# LED-PCB_DIG0.net
KiCad netlist of a schematic drawn in Altium Designer
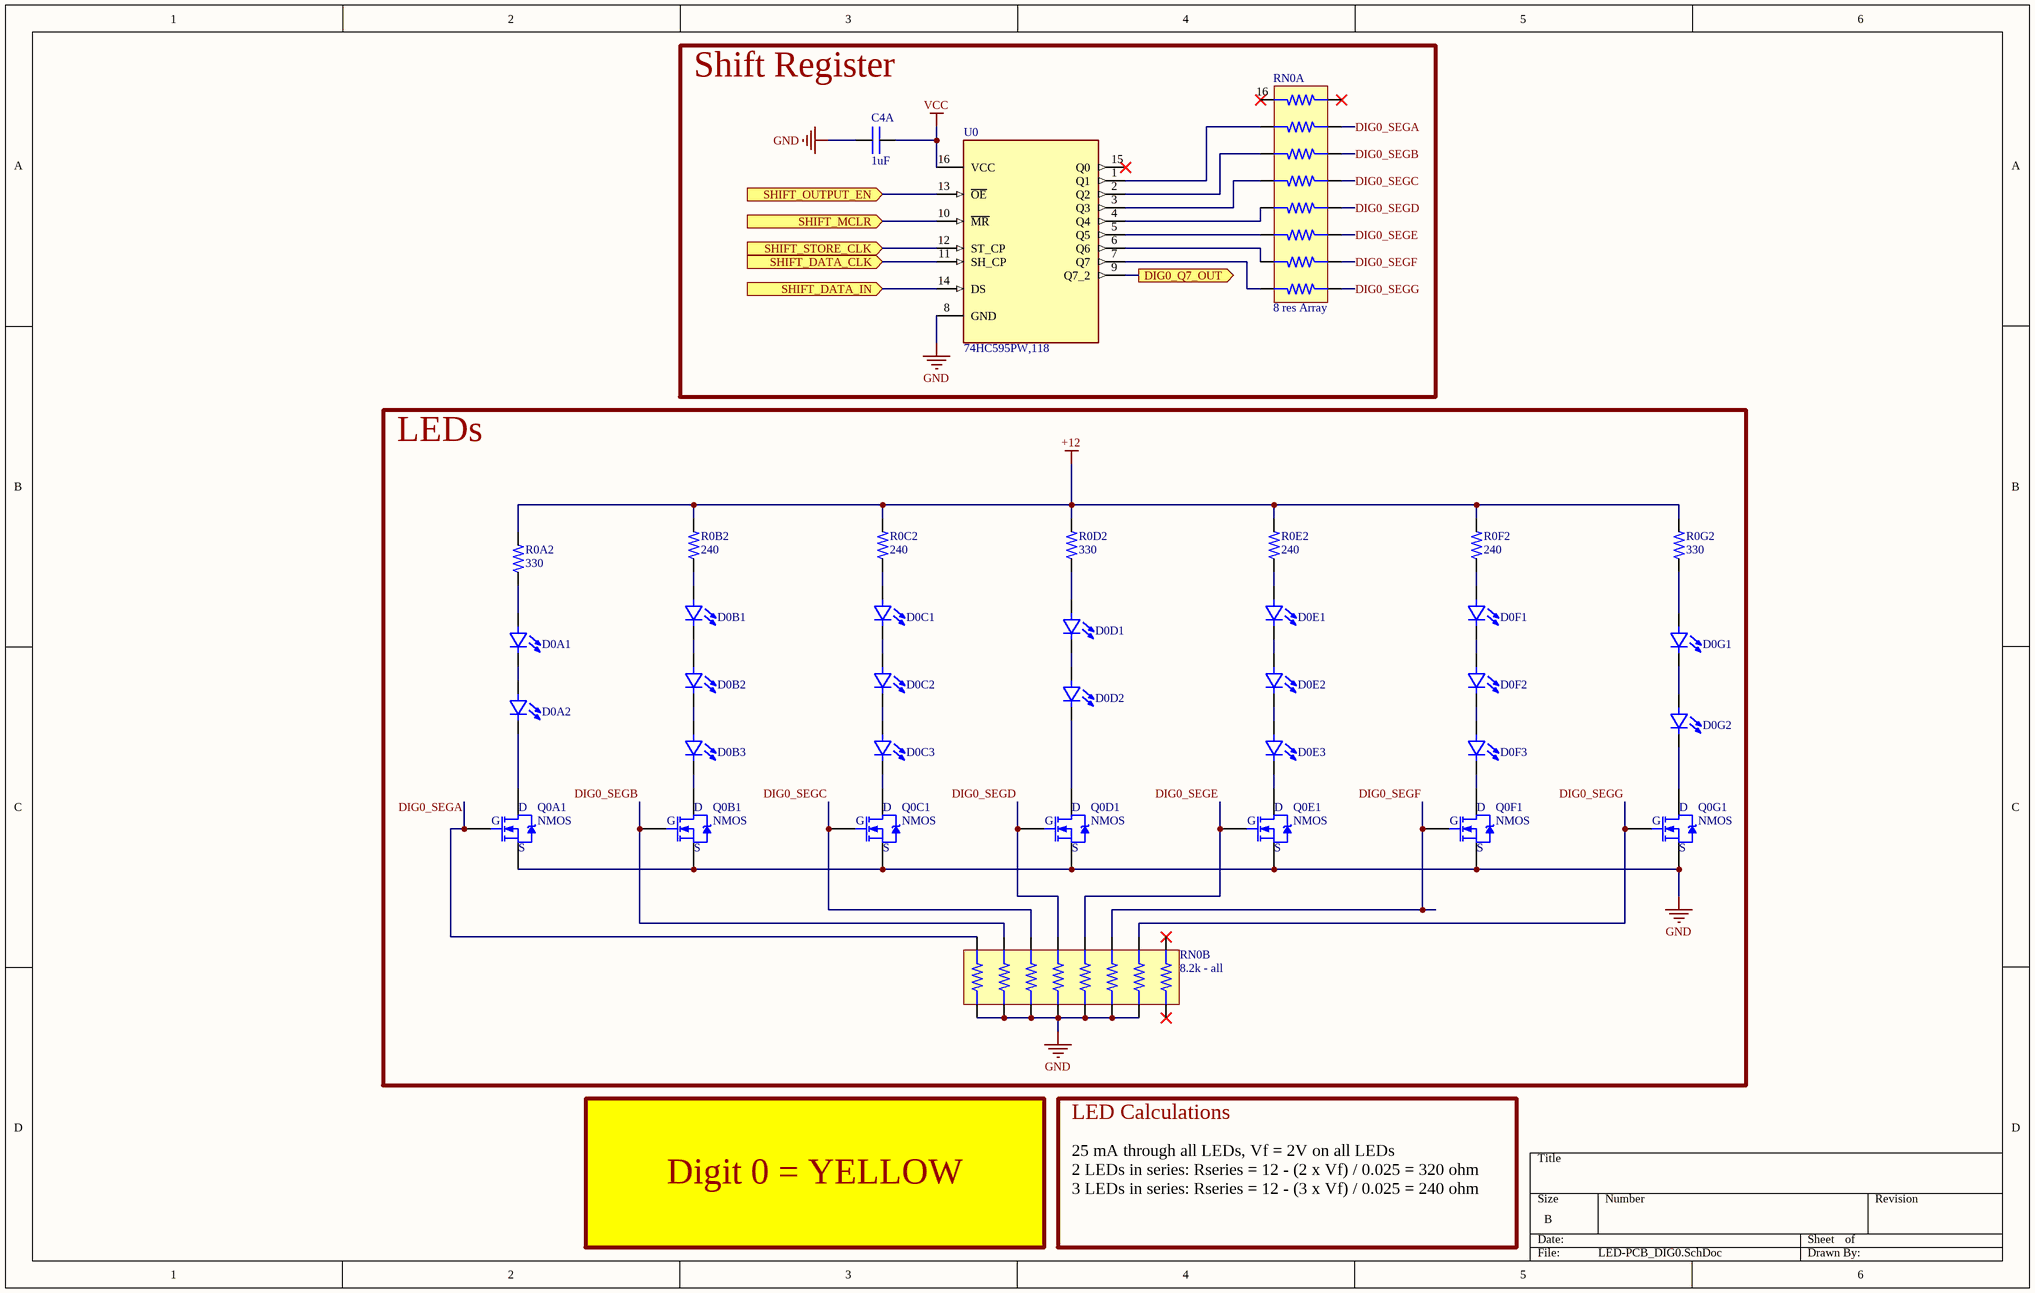
[diagram p0: LED-PCB_DIG0.SchDoc]

(export (version "E")
  (design (tool "Eeschema 10.0.6"))
  (components
    (comp (ref "C4A")
      (value "1uF")
      (footprint "sinking-clock:0402 CAP")
      (description "Capaicitor")
      (fields (field (name "PART NUMBER") "CL05A105KP5NNNC") (field (name "Comment") "CAP"))
      (libsource (lib "sinking-clock") (part "CAP"))
    )
    (comp (ref "D0A1")
      (value "LED - single")
      (footprint "sinking-clock:LED - 0603")
      (fields (field (name "PART NUMBER") "150060RS75000"))
      (libsource (lib "sinking-clock") (part "LED - single"))
    )
    (comp (ref "D0A2")
      (value "LED - single")
      (footprint "sinking-clock:LED - 0603")
      (fields (field (name "PART NUMBER") "150060RS75000"))
      (libsource (lib "sinking-clock") (part "LED - single"))
    )
    (comp (ref "D0B1")
      (value "LED - single")
      (footprint "sinking-clock:LED - 0603")
      (fields (field (name "PART NUMBER") "150060RS75000"))
      (libsource (lib "sinking-clock") (part "LED - single"))
    )
    (comp (ref "D0B2")
      (value "LED - single")
      (footprint "sinking-clock:LED - 0603")
      (fields (field (name "PART NUMBER") "150060RS75000"))
      (libsource (lib "sinking-clock") (part "LED - single"))
    )
    (comp (ref "D0B3")
      (value "LED - single")
      (footprint "sinking-clock:LED - 0603")
      (fields (field (name "PART NUMBER") "150060RS75000"))
      (libsource (lib "sinking-clock") (part "LED - single"))
    )
    (comp (ref "D0C1")
      (value "LED - single")
      (footprint "sinking-clock:LED - 0603")
      (fields (field (name "PART NUMBER") "150060RS75000"))
      (libsource (lib "sinking-clock") (part "LED - single"))
    )
    (comp (ref "D0C2")
      (value "LED - single")
      (footprint "sinking-clock:LED - 0603")
      (fields (field (name "PART NUMBER") "150060RS75000"))
      (libsource (lib "sinking-clock") (part "LED - single"))
    )
    (comp (ref "D0C3")
      (value "LED - single")
      (footprint "sinking-clock:LED - 0603")
      (fields (field (name "PART NUMBER") "150060RS75000"))
      (libsource (lib "sinking-clock") (part "LED - single"))
    )
    (comp (ref "D0D1")
      (value "LED - single")
      (footprint "sinking-clock:LED - 0603")
      (fields (field (name "PART NUMBER") "150060RS75000"))
      (libsource (lib "sinking-clock") (part "LED - single"))
    )
    (comp (ref "D0D2")
      (value "LED - single")
      (footprint "sinking-clock:LED - 0603")
      (fields (field (name "PART NUMBER") "150060RS75000"))
      (libsource (lib "sinking-clock") (part "LED - single"))
    )
    (comp (ref "D0E1")
      (value "LED - single")
      (footprint "sinking-clock:LED - 0603")
      (fields (field (name "PART NUMBER") "150060RS75000"))
      (libsource (lib "sinking-clock") (part "LED - single"))
    )
    (comp (ref "D0E2")
      (value "LED - single")
      (footprint "sinking-clock:LED - 0603")
      (fields (field (name "PART NUMBER") "150060RS75000"))
      (libsource (lib "sinking-clock") (part "LED - single"))
    )
    (comp (ref "D0E3")
      (value "LED - single")
      (footprint "sinking-clock:LED - 0603")
      (fields (field (name "PART NUMBER") "150060RS75000"))
      (libsource (lib "sinking-clock") (part "LED - single"))
    )
    (comp (ref "D0F1")
      (value "LED - single")
      (footprint "sinking-clock:LED - 0603")
      (fields (field (name "PART NUMBER") "150060RS75000"))
      (libsource (lib "sinking-clock") (part "LED - single"))
    )
    (comp (ref "D0F2")
      (value "LED - single")
      (footprint "sinking-clock:LED - 0603")
      (fields (field (name "PART NUMBER") "150060RS75000"))
      (libsource (lib "sinking-clock") (part "LED - single"))
    )
    (comp (ref "D0F3")
      (value "LED - single")
      (footprint "sinking-clock:LED - 0603")
      (fields (field (name "PART NUMBER") "150060RS75000"))
      (libsource (lib "sinking-clock") (part "LED - single"))
    )
    (comp (ref "D0G1")
      (value "LED - single")
      (footprint "sinking-clock:LED - 0603")
      (fields (field (name "PART NUMBER") "150060RS75000"))
      (libsource (lib "sinking-clock") (part "LED - single"))
    )
    (comp (ref "D0G2")
      (value "LED - single")
      (footprint "sinking-clock:LED - 0603")
      (fields (field (name "PART NUMBER") "150060RS75000"))
      (libsource (lib "sinking-clock") (part "LED - single"))
    )
    (comp (ref "Q0A1")
      (value "NMOS")
      (footprint "sinking-clock:SOT-23")
      (description "N-Channel MOSFET")
      (fields (field (name "PART NUMBER") "DMN63D8L"))
      (libsource (lib "sinking-clock") (part "NMOS"))
    )
    (comp (ref "Q0B1")
      (value "NMOS")
      (footprint "sinking-clock:SOT-23")
      (description "N-Channel MOSFET")
      (fields (field (name "PART NUMBER") "DMN63D8L"))
      (libsource (lib "sinking-clock") (part "NMOS"))
    )
    (comp (ref "Q0C1")
      (value "NMOS")
      (footprint "sinking-clock:SOT-23")
      (description "N-Channel MOSFET")
      (fields (field (name "PART NUMBER") "DMN63D8L"))
      (libsource (lib "sinking-clock") (part "NMOS"))
    )
    (comp (ref "Q0D1")
      (value "NMOS")
      (footprint "sinking-clock:SOT-23")
      (description "N-Channel MOSFET")
      (fields (field (name "PART NUMBER") "DMN63D8L"))
      (libsource (lib "sinking-clock") (part "NMOS"))
    )
    (comp (ref "Q0E1")
      (value "NMOS")
      (footprint "sinking-clock:SOT-23")
      (description "N-Channel MOSFET")
      (fields (field (name "PART NUMBER") "DMN63D8L"))
      (libsource (lib "sinking-clock") (part "NMOS"))
    )
    (comp (ref "Q0F1")
      (value "NMOS")
      (footprint "sinking-clock:SOT-23")
      (description "N-Channel MOSFET")
      (fields (field (name "PART NUMBER") "DMN63D8L"))
      (libsource (lib "sinking-clock") (part "NMOS"))
    )
    (comp (ref "Q0G1")
      (value "NMOS")
      (footprint "sinking-clock:SOT-23")
      (description "N-Channel MOSFET")
      (fields (field (name "PART NUMBER") "DMN63D8L"))
      (libsource (lib "sinking-clock") (part "NMOS"))
    )
    (comp (ref "R0A2")
      (value "330")
      (footprint "sinking-clock:0402 RES")
      (description "Resistor")
      (fields (field (name "PART NUMBER") "RC0402JR-13330RL") (field (name "Comment") "RES"))
      (libsource (lib "sinking-clock") (part "RES"))
    )
    (comp (ref "R0B2")
      (value "240")
      (footprint "sinking-clock:0402 RES")
      (description "Resistor")
      (fields (field (name "PART NUMBER") "RC0402FR-07240RL") (field (name "Comment") "RES"))
      (libsource (lib "sinking-clock") (part "RES"))
    )
    (comp (ref "R0C2")
      (value "240")
      (footprint "sinking-clock:0402 RES")
      (description "Resistor")
      (fields (field (name "PART NUMBER") "RC0402FR-07240RL") (field (name "Comment") "RES"))
      (libsource (lib "sinking-clock") (part "RES"))
    )
    (comp (ref "R0D2")
      (value "330")
      (footprint "sinking-clock:0402 RES")
      (description "Resistor")
      (fields (field (name "PART NUMBER") "RC0402JR-13330RL") (field (name "Comment") "RES"))
      (libsource (lib "sinking-clock") (part "RES"))
    )
    (comp (ref "R0E2")
      (value "240")
      (footprint "sinking-clock:0402 RES")
      (description "Resistor")
      (fields (field (name "PART NUMBER") "RC0402FR-07240RL") (field (name "Comment") "RES"))
      (libsource (lib "sinking-clock") (part "RES"))
    )
    (comp (ref "R0F2")
      (value "240")
      (footprint "sinking-clock:0402 RES")
      (description "Resistor")
      (fields (field (name "PART NUMBER") "RC0402FR-07240RL") (field (name "Comment") "RES"))
      (libsource (lib "sinking-clock") (part "RES"))
    )
    (comp (ref "R0G2")
      (value "330")
      (footprint "sinking-clock:0402 RES")
      (description "Resistor")
      (fields (field (name "PART NUMBER") "RC0402JR-13330RL") (field (name "Comment") "RES"))
      (libsource (lib "sinking-clock") (part "RES"))
    )
    (comp (ref "RN0A")
      (value "8 res Array")
      (footprint "sinking-clock:EXB2HV331JV")
      (libsource (lib "sinking-clock") (part "8 res Array"))
    )
    (comp (ref "RN0B")
      (value "8.2k - all")
      (footprint "sinking-clock:MNR18ERAPJ822")
      (fields (field (name "PART NUMBER") "MNR18ERAPJ822"))
      (libsource (lib "sinking-clock") (part "MNR18ERAPJ822"))
    )
    (comp (ref "U0")
      (value "74HC595PW,118")
      (footprint "sinking-clock:16-TSSOP")
      (description "Shift Shift Register 1 Element 8 Bit 16-TSSOP")
      (libsource (lib "sinking-clock") (part "74HC595PW,118"))
    )
  )
  (nets
    (net (code "1") (name "+12") (class "Default")
      (node (ref "R0A2") (pin "2") (pinfunction "2_2") (pintype "passive"))
      (node (ref "R0B2") (pin "2") (pinfunction "2_2") (pintype "passive"))
      (node (ref "R0C2") (pin "2") (pinfunction "2_2") (pintype "passive"))
      (node (ref "R0D2") (pin "2") (pinfunction "2_2") (pintype "passive"))
      (node (ref "R0E2") (pin "2") (pinfunction "2_2") (pintype "passive"))
      (node (ref "R0F2") (pin "2") (pinfunction "2_2") (pintype "passive"))
      (node (ref "R0G2") (pin "2") (pinfunction "2_2") (pintype "passive"))
    )
    (net (code "2") (name "/DIG0_Q7_OUT") (class "Default")
      (node (ref "U0") (pin "9") (pinfunction "Q7_2_9") (pintype "output"))
    )
    (net (code "3") (name "/DIG0_SEGA") (class "Default")
      (node (ref "Q0A1") (pin "1") (pinfunction "G_1") (pintype "passive"))
      (node (ref "RN0A") (pin "2") (pinfunction "2_2") (pintype "passive"))
      (node (ref "RN0B") (pin "16") (pinfunction "16_16") (pintype "passive"))
    )
    (net (code "4") (name "/DIG0_SEGB") (class "Default")
      (node (ref "Q0B1") (pin "1") (pinfunction "G_1") (pintype "passive"))
      (node (ref "RN0A") (pin "3") (pinfunction "3_3") (pintype "passive"))
      (node (ref "RN0B") (pin "15") (pinfunction "15_15") (pintype "passive"))
    )
    (net (code "5") (name "/DIG0_SEGC") (class "Default")
      (node (ref "Q0C1") (pin "1") (pinfunction "G_1") (pintype "passive"))
      (node (ref "RN0A") (pin "4") (pinfunction "4_4") (pintype "passive"))
      (node (ref "RN0B") (pin "14") (pinfunction "14_14") (pintype "passive"))
    )
    (net (code "6") (name "/DIG0_SEGD") (class "Default")
      (node (ref "Q0D1") (pin "1") (pinfunction "G_1") (pintype "passive"))
      (node (ref "RN0A") (pin "5") (pinfunction "5_5") (pintype "passive"))
      (node (ref "RN0B") (pin "13") (pinfunction "13_13") (pintype "passive"))
    )
    (net (code "7") (name "/DIG0_SEGE") (class "Default")
      (node (ref "Q0E1") (pin "1") (pinfunction "G_1") (pintype "passive"))
      (node (ref "RN0A") (pin "6") (pinfunction "6_6") (pintype "passive"))
      (node (ref "RN0B") (pin "12") (pinfunction "12_12") (pintype "passive"))
    )
    (net (code "8") (name "/DIG0_SEGF") (class "Default")
      (node (ref "Q0F1") (pin "1") (pinfunction "G_1") (pintype "passive"))
      (node (ref "RN0A") (pin "7") (pinfunction "7_7") (pintype "passive"))
      (node (ref "RN0B") (pin "11") (pinfunction "11_11") (pintype "passive"))
    )
    (net (code "9") (name "/DIG0_SEGG") (class "Default")
      (node (ref "Q0G1") (pin "1") (pinfunction "G_1") (pintype "passive"))
      (node (ref "RN0A") (pin "8") (pinfunction "8_8") (pintype "passive"))
      (node (ref "RN0B") (pin "10") (pinfunction "10_10") (pintype "passive"))
    )
    (net (code "10") (name "/SHIFT_DATA_CLK") (class "Default")
      (node (ref "U0") (pin "11") (pinfunction "SH_CP_11") (pintype "input"))
    )
    (net (code "11") (name "/SHIFT_DATA_IN") (class "Default")
      (node (ref "U0") (pin "14") (pinfunction "DS_14") (pintype "input"))
    )
    (net (code "12") (name "/SHIFT_MCLR") (class "Default")
      (node (ref "U0") (pin "10") (pinfunction "~{MR}_10") (pintype "input"))
    )
    (net (code "13") (name "/SHIFT_OUTPUT_EN") (class "Default")
      (node (ref "U0") (pin "13") (pinfunction "~{OE}_13") (pintype "input"))
    )
    (net (code "14") (name "/SHIFT_STORE_CLK") (class "Default")
      (node (ref "U0") (pin "12") (pinfunction "ST_CP_12") (pintype "input"))
    )
    (net (code "15") (name "GND") (class "Default")
      (node (ref "C4A") (pin "1") (pinfunction "1_1") (pintype "passive"))
      (node (ref "Q0A1") (pin "2") (pinfunction "S_2") (pintype "passive"))
      (node (ref "Q0B1") (pin "2") (pinfunction "S_2") (pintype "passive"))
      (node (ref "Q0C1") (pin "2") (pinfunction "S_2") (pintype "passive"))
      (node (ref "Q0D1") (pin "2") (pinfunction "S_2") (pintype "passive"))
      (node (ref "Q0E1") (pin "2") (pinfunction "S_2") (pintype "passive"))
      (node (ref "Q0F1") (pin "2") (pinfunction "S_2") (pintype "passive"))
      (node (ref "Q0G1") (pin "2") (pinfunction "S_2") (pintype "passive"))
      (node (ref "RN0B") (pin "1") (pinfunction "1_1") (pintype "passive"))
      (node (ref "RN0B") (pin "2") (pinfunction "2_2") (pintype "passive"))
      (node (ref "RN0B") (pin "3") (pinfunction "3_3") (pintype "passive"))
      (node (ref "RN0B") (pin "4") (pinfunction "4_4") (pintype "passive"))
      (node (ref "RN0B") (pin "5") (pinfunction "5_5") (pintype "passive"))
      (node (ref "RN0B") (pin "6") (pinfunction "6_6") (pintype "passive"))
      (node (ref "RN0B") (pin "7") (pinfunction "7_7") (pintype "passive"))
      (node (ref "U0") (pin "8") (pinfunction "GND_8") (pintype "passive"))
    )
    (net (code "16") (name "Net-(D0A1-A)") (class "Default")
      (node (ref "D0A1") (pin "1") (pinfunction "A_1") (pintype "passive"))
      (node (ref "R0A2") (pin "1") (pinfunction "1_1") (pintype "passive"))
    )
    (net (code "17") (name "Net-(D0A1-C)") (class "Default")
      (node (ref "D0A1") (pin "2") (pinfunction "C_2") (pintype "passive"))
      (node (ref "D0A2") (pin "1") (pinfunction "A_1") (pintype "passive"))
    )
    (net (code "18") (name "Net-(D0A2-C)") (class "Default")
      (node (ref "D0A2") (pin "2") (pinfunction "C_2") (pintype "passive"))
      (node (ref "Q0A1") (pin "3") (pinfunction "D_3") (pintype "passive"))
    )
    (net (code "19") (name "Net-(D0B1-A)") (class "Default")
      (node (ref "D0B1") (pin "1") (pinfunction "A_1") (pintype "passive"))
      (node (ref "R0B2") (pin "1") (pinfunction "1_1") (pintype "passive"))
    )
    (net (code "20") (name "Net-(D0B1-C)") (class "Default")
      (node (ref "D0B1") (pin "2") (pinfunction "C_2") (pintype "passive"))
      (node (ref "D0B2") (pin "1") (pinfunction "A_1") (pintype "passive"))
    )
    (net (code "21") (name "Net-(D0B2-C)") (class "Default")
      (node (ref "D0B2") (pin "2") (pinfunction "C_2") (pintype "passive"))
      (node (ref "D0B3") (pin "1") (pinfunction "A_1") (pintype "passive"))
    )
    (net (code "22") (name "Net-(D0B3-C)") (class "Default")
      (node (ref "D0B3") (pin "2") (pinfunction "C_2") (pintype "passive"))
      (node (ref "Q0B1") (pin "3") (pinfunction "D_3") (pintype "passive"))
    )
    (net (code "23") (name "Net-(D0C1-A)") (class "Default")
      (node (ref "D0C1") (pin "1") (pinfunction "A_1") (pintype "passive"))
      (node (ref "R0C2") (pin "1") (pinfunction "1_1") (pintype "passive"))
    )
    (net (code "24") (name "Net-(D0C1-C)") (class "Default")
      (node (ref "D0C1") (pin "2") (pinfunction "C_2") (pintype "passive"))
      (node (ref "D0C2") (pin "1") (pinfunction "A_1") (pintype "passive"))
    )
    (net (code "25") (name "Net-(D0C2-C)") (class "Default")
      (node (ref "D0C2") (pin "2") (pinfunction "C_2") (pintype "passive"))
      (node (ref "D0C3") (pin "1") (pinfunction "A_1") (pintype "passive"))
    )
    (net (code "26") (name "Net-(D0C3-C)") (class "Default")
      (node (ref "D0C3") (pin "2") (pinfunction "C_2") (pintype "passive"))
      (node (ref "Q0C1") (pin "3") (pinfunction "D_3") (pintype "passive"))
    )
    (net (code "27") (name "Net-(D0D1-A)") (class "Default")
      (node (ref "D0D1") (pin "1") (pinfunction "A_1") (pintype "passive"))
      (node (ref "R0D2") (pin "1") (pinfunction "1_1") (pintype "passive"))
    )
    (net (code "28") (name "Net-(D0D1-C)") (class "Default")
      (node (ref "D0D1") (pin "2") (pinfunction "C_2") (pintype "passive"))
      (node (ref "D0D2") (pin "1") (pinfunction "A_1") (pintype "passive"))
    )
    (net (code "29") (name "Net-(D0D2-C)") (class "Default")
      (node (ref "D0D2") (pin "2") (pinfunction "C_2") (pintype "passive"))
      (node (ref "Q0D1") (pin "3") (pinfunction "D_3") (pintype "passive"))
    )
    (net (code "30") (name "Net-(D0E1-A)") (class "Default")
      (node (ref "D0E1") (pin "1") (pinfunction "A_1") (pintype "passive"))
      (node (ref "R0E2") (pin "1") (pinfunction "1_1") (pintype "passive"))
    )
    (net (code "31") (name "Net-(D0E1-C)") (class "Default")
      (node (ref "D0E1") (pin "2") (pinfunction "C_2") (pintype "passive"))
      (node (ref "D0E2") (pin "1") (pinfunction "A_1") (pintype "passive"))
    )
    (net (code "32") (name "Net-(D0E2-C)") (class "Default")
      (node (ref "D0E2") (pin "2") (pinfunction "C_2") (pintype "passive"))
      (node (ref "D0E3") (pin "1") (pinfunction "A_1") (pintype "passive"))
    )
    (net (code "33") (name "Net-(D0E3-C)") (class "Default")
      (node (ref "D0E3") (pin "2") (pinfunction "C_2") (pintype "passive"))
      (node (ref "Q0E1") (pin "3") (pinfunction "D_3") (pintype "passive"))
    )
    (net (code "34") (name "Net-(D0F1-A)") (class "Default")
      (node (ref "D0F1") (pin "1") (pinfunction "A_1") (pintype "passive"))
      (node (ref "R0F2") (pin "1") (pinfunction "1_1") (pintype "passive"))
    )
    (net (code "35") (name "Net-(D0F1-C)") (class "Default")
      (node (ref "D0F1") (pin "2") (pinfunction "C_2") (pintype "passive"))
      (node (ref "D0F2") (pin "1") (pinfunction "A_1") (pintype "passive"))
    )
    (net (code "36") (name "Net-(D0F2-C)") (class "Default")
      (node (ref "D0F2") (pin "2") (pinfunction "C_2") (pintype "passive"))
      (node (ref "D0F3") (pin "1") (pinfunction "A_1") (pintype "passive"))
    )
    (net (code "37") (name "Net-(D0F3-C)") (class "Default")
      (node (ref "D0F3") (pin "2") (pinfunction "C_2") (pintype "passive"))
      (node (ref "Q0F1") (pin "3") (pinfunction "D_3") (pintype "passive"))
    )
    (net (code "38") (name "Net-(D0G1-A)") (class "Default")
      (node (ref "D0G1") (pin "1") (pinfunction "A_1") (pintype "passive"))
      (node (ref "R0G2") (pin "1") (pinfunction "1_1") (pintype "passive"))
    )
    (net (code "39") (name "Net-(D0G1-C)") (class "Default")
      (node (ref "D0G1") (pin "2") (pinfunction "C_2") (pintype "passive"))
      (node (ref "D0G2") (pin "1") (pinfunction "A_1") (pintype "passive"))
    )
    (net (code "40") (name "Net-(D0G2-C)") (class "Default")
      (node (ref "D0G2") (pin "2") (pinfunction "C_2") (pintype "passive"))
      (node (ref "Q0G1") (pin "3") (pinfunction "D_3") (pintype "passive"))
    )
    (net (code "41") (name "Net-(U0-Q1)") (class "Default")
      (node (ref "RN0A") (pin "15") (pinfunction "15_15") (pintype "passive"))
      (node (ref "U0") (pin "1") (pinfunction "Q1_1") (pintype "output"))
    )
    (net (code "42") (name "Net-(U0-Q2)") (class "Default")
      (node (ref "RN0A") (pin "14") (pinfunction "14_14") (pintype "passive"))
      (node (ref "U0") (pin "2") (pinfunction "Q2_2") (pintype "output"))
    )
    (net (code "43") (name "Net-(U0-Q3)") (class "Default")
      (node (ref "RN0A") (pin "13") (pinfunction "13_13") (pintype "passive"))
      (node (ref "U0") (pin "3") (pinfunction "Q3_3") (pintype "output"))
    )
    (net (code "44") (name "Net-(U0-Q4)") (class "Default")
      (node (ref "RN0A") (pin "12") (pinfunction "12_12") (pintype "passive"))
      (node (ref "U0") (pin "4") (pinfunction "Q4_4") (pintype "output"))
    )
    (net (code "45") (name "Net-(U0-Q5)") (class "Default")
      (node (ref "RN0A") (pin "11") (pinfunction "11_11") (pintype "passive"))
      (node (ref "U0") (pin "5") (pinfunction "Q5_5") (pintype "output"))
    )
    (net (code "46") (name "Net-(U0-Q6)") (class "Default")
      (node (ref "RN0A") (pin "10") (pinfunction "10_10") (pintype "passive"))
      (node (ref "U0") (pin "6") (pinfunction "Q6_6") (pintype "output"))
    )
    (net (code "47") (name "Net-(U0-Q7)") (class "Default")
      (node (ref "RN0A") (pin "9") (pinfunction "9_9") (pintype "passive"))
      (node (ref "U0") (pin "7") (pinfunction "Q7_7") (pintype "output"))
    )
    (net (code "48") (name "VCC") (class "Default")
      (node (ref "C4A") (pin "2") (pinfunction "2_2") (pintype "passive"))
      (node (ref "U0") (pin "16") (pinfunction "VCC_16") (pintype "power_in"))
    )
    (net (code "49") (name "unconnected-(RN0A-Pad1)") (class "Default")
      (node (ref "RN0A") (pin "1") (pinfunction "1_1") (pintype "passive+no_connect"))
    )
    (net (code "50") (name "unconnected-(RN0A-Pad16)") (class "Default")
      (node (ref "RN0A") (pin "16") (pinfunction "16_16") (pintype "passive+no_connect"))
    )
    (net (code "51") (name "unconnected-(RN0B-Pad8)") (class "Default")
      (node (ref "RN0B") (pin "8") (pinfunction "8_8") (pintype "passive+no_connect"))
    )
    (net (code "52") (name "unconnected-(RN0B-Pad9)") (class "Default")
      (node (ref "RN0B") (pin "9") (pinfunction "9_9") (pintype "passive+no_connect"))
    )
    (net (code "53") (name "unconnected-(U0-Q0-Pad15)") (class "Default")
      (node (ref "U0") (pin "15") (pinfunction "Q0_15") (pintype "output+no_connect"))
    )
  )
)
